# ts4231-breakout-module.net
KiCad netlist of a schematic drawn in EAGLE
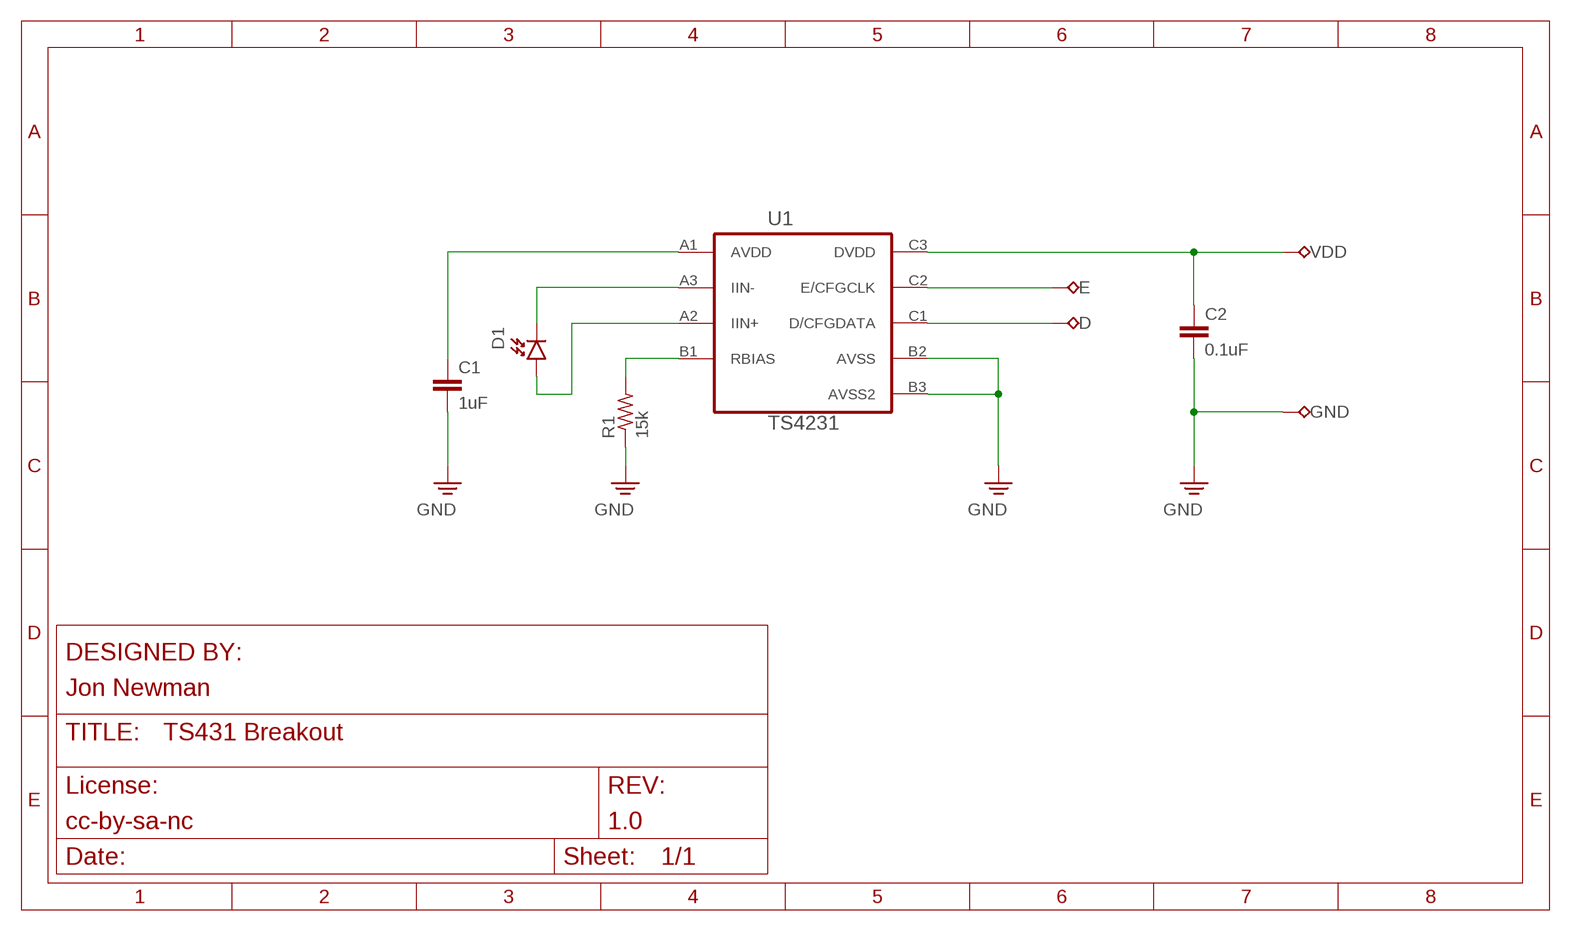
[diagram p0: schematic, sheet 1]

(export (version "E")
  (design (tool "Eeschema 10.0.6"))
  (components
    (comp (ref "C1")
      (value "1uF")
      (footprint "eagle-import:0402")
      (libsource (lib "eagle-import") (part "C_0402"))
    )
    (comp (ref "C2")
      (value "0.1uF")
      (footprint "eagle-import:0201")
      (libsource (lib "eagle-import") (part "C_0201"))
    )
    (comp (ref "D")
      (value "TP_TP23MIL")
      (footprint "eagle-import:TP23MIL")
      (libsource (lib "eagle-import") (part "TP_TP23MIL"))
    )
    (comp (ref "D1")
      (value "PHOTODIODE_0805")
      (footprint "eagle-import:0805")
      (libsource (lib "eagle-import") (part "PHOTODIODE_0805"))
    )
    (comp (ref "E")
      (value "TP_TP23MIL")
      (footprint "eagle-import:TP23MIL")
      (libsource (lib "eagle-import") (part "TP_TP23MIL"))
    )
    (comp (ref "GND")
      (value "TP_TP23MIL")
      (footprint "eagle-import:TP23MIL")
      (libsource (lib "eagle-import") (part "TP_TP23MIL"))
    )
    (comp (ref "R1")
      (value "15k")
      (footprint "eagle-import:0201")
      (libsource (lib "eagle-import") (part "R_0201"))
    )
    (comp (ref "U1")
      (value "TS4231")
      (footprint "eagle-import:WLCSP3X3")
      (libsource (lib "eagle-import") (part "TS4231"))
    )
    (comp (ref "VDD")
      (value "TP_TP23MIL")
      (footprint "eagle-import:TP23MIL")
      (libsource (lib "eagle-import") (part "TP_TP23MIL"))
    )
  )
  (nets
    (net (code "1") (name "GND") (class "Default")
      (node (ref "C1") (pin "2") (pinfunction "2_2") (pintype "passive"))
      (node (ref "C2") (pin "2") (pinfunction "2_2") (pintype "passive"))
      (node (ref "GND") (pin "P$1") (pinfunction "TP_P$1") (pintype "bidirectional"))
      (node (ref "R1") (pin "1") (pinfunction "1_1") (pintype "passive"))
      (node (ref "U1") (pin "B2") (pinfunction "AVSS_B2") (pintype "passive"))
      (node (ref "U1") (pin "B3") (pinfunction "AVSS2_B3") (pintype "passive"))
    )
    (net (code "2") (name "Net-(D-TP)") (class "Default")
      (node (ref "D") (pin "P$1") (pinfunction "TP_P$1") (pintype "bidirectional"))
      (node (ref "U1") (pin "C1") (pinfunction "D/CFGDATA_C1") (pintype "bidirectional"))
    )
    (net (code "3") (name "Net-(D1-A)") (class "Default")
      (node (ref "D1") (pin "1") (pinfunction "A_1") (pintype "passive"))
      (node (ref "U1") (pin "A2") (pinfunction "IIN+_A2") (pintype "input"))
    )
    (net (code "4") (name "Net-(D1-C)") (class "Default")
      (node (ref "D1") (pin "2") (pinfunction "C_2") (pintype "passive"))
      (node (ref "U1") (pin "A3") (pinfunction "IIN-_A3") (pintype "input"))
    )
    (net (code "5") (name "Net-(E-TP)") (class "Default")
      (node (ref "E") (pin "P$1") (pinfunction "TP_P$1") (pintype "bidirectional"))
      (node (ref "U1") (pin "C2") (pinfunction "E/CFGCLK_C2") (pintype "bidirectional"))
    )
    (net (code "6") (name "Net-(U1-AVDD)") (class "Default")
      (node (ref "C1") (pin "1") (pinfunction "1_1") (pintype "passive"))
      (node (ref "U1") (pin "A1") (pinfunction "AVDD_A1") (pintype "power_in"))
    )
    (net (code "7") (name "Net-(U1-DVDD)") (class "Default")
      (node (ref "C2") (pin "1") (pinfunction "1_1") (pintype "passive"))
      (node (ref "U1") (pin "C3") (pinfunction "DVDD_C3") (pintype "power_in"))
      (node (ref "VDD") (pin "P$1") (pinfunction "TP_P$1") (pintype "bidirectional"))
    )
    (net (code "8") (name "Net-(U1-RBIAS)") (class "Default")
      (node (ref "R1") (pin "2") (pinfunction "2_2") (pintype "passive"))
      (node (ref "U1") (pin "B1") (pinfunction "RBIAS_B1") (pintype "passive"))
    )
  )
)
